# SJA1105Q_PINOUT.net
KiCad netlist of a schematic drawn in Altium Designer
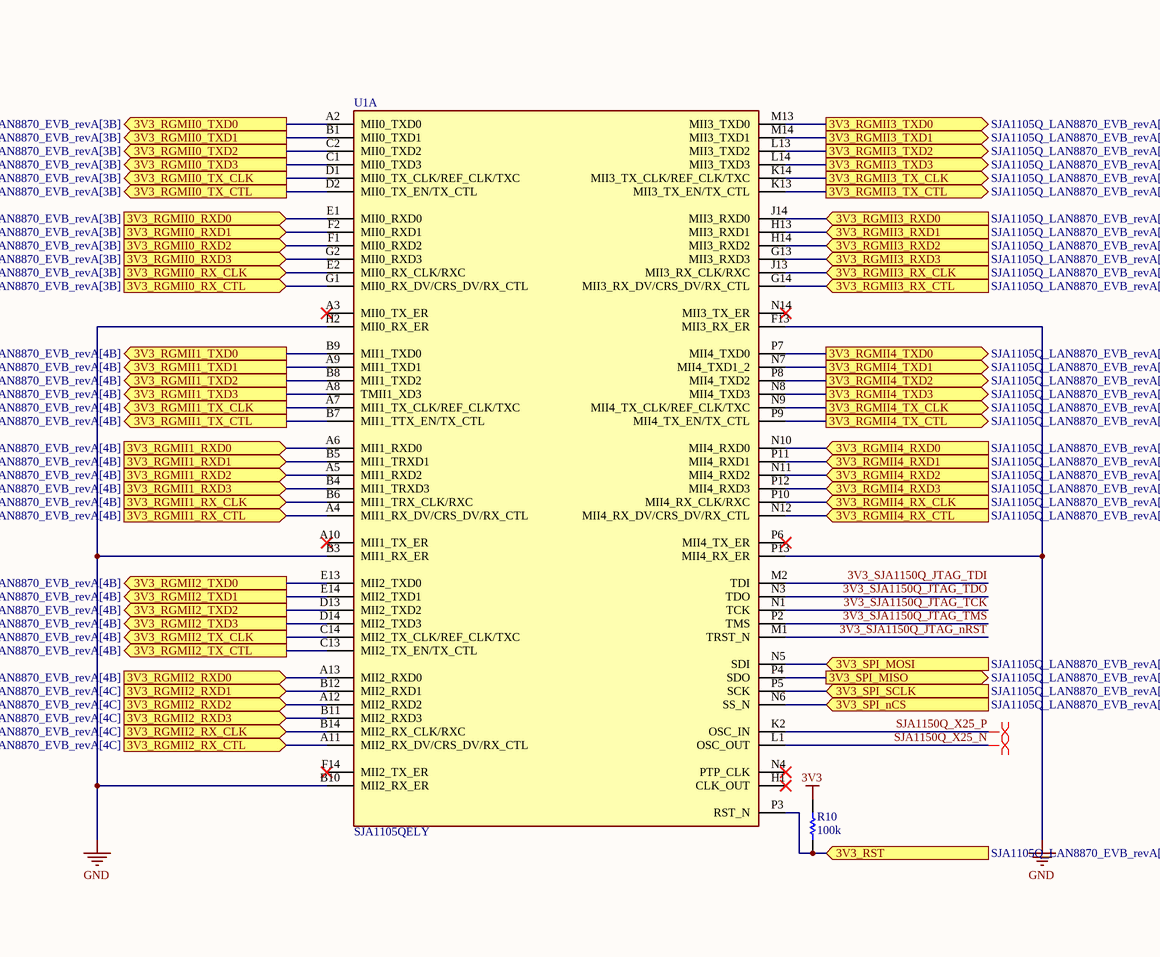
[diagram p0: SJA1105Q_PINOUT.SchDoc, top left]
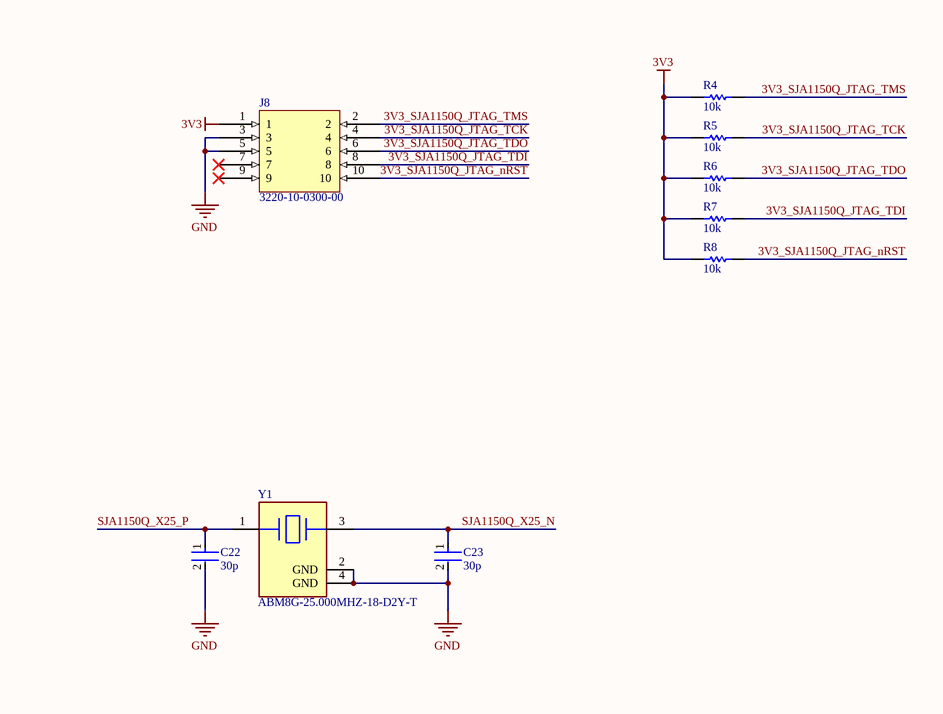
[diagram p1: SJA1105Q_PINOUT.SchDoc, top right]
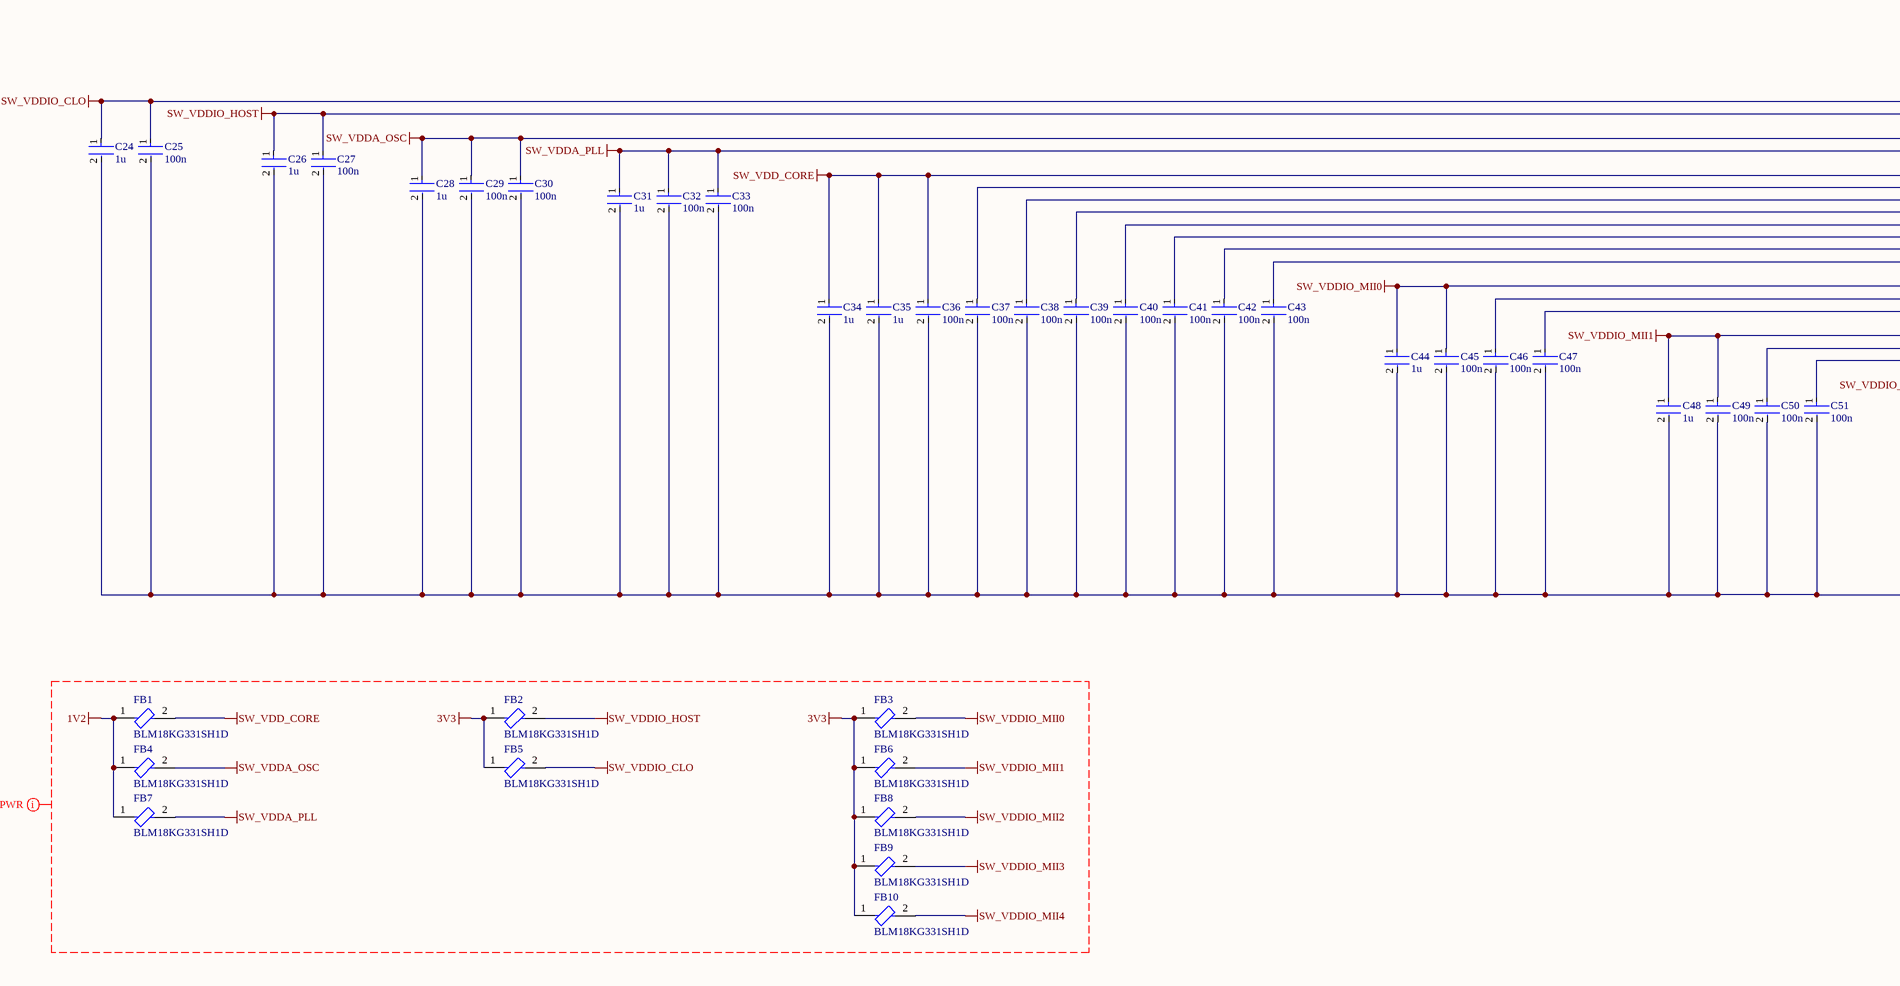
[diagram p2: SJA1105Q_PINOUT.SchDoc, bottom left]
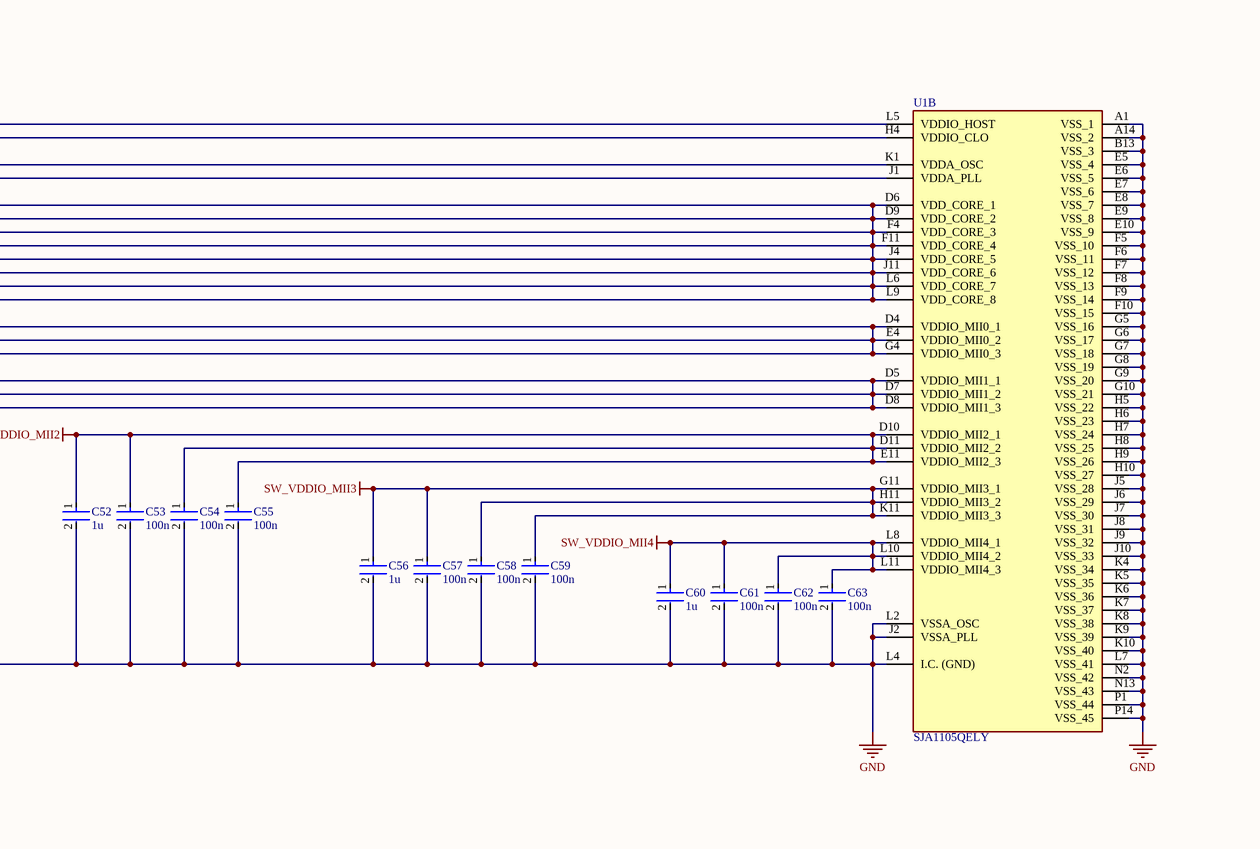
[diagram p3: SJA1105Q_PINOUT.SchDoc, bottom right]

(export (version "E")
  (design (tool "Eeschema 10.0.6"))
  (components
    (comp (ref "C22")
      (value "30p")
      (footprint "FP-0402-L_1_0_0_05-W_0_5-IPC_A")
      (description "LARGE PADS, 0402 CAP, CHANGE COMMENT TO MATCH REAL P/N")
      (libsource (lib "Space Concordia") (part "b4654b650e69147ec39a6b967a45e02"))
    )
    (comp (ref "C23")
      (value "30p")
      (footprint "FP-0402-L_1_0_0_05-W_0_5-IPC_A")
      (description "LARGE PADS, 0402 CAP, CHANGE COMMENT TO MATCH REAL P/N")
      (libsource (lib "Space Concordia") (part "b4654b650e69147ec39a6b967a45e02"))
    )
    (comp (ref "C24")
      (value "1u")
      (footprint "FP-0402-L_1_0_0_05-W_0_5-IPC_A")
      (description "LARGE PADS, 0402 CAP, CHANGE COMMENT TO MATCH REAL P/N")
      (libsource (lib "Space Concordia") (part "b4654b650e69147ec39a6b967a45e02"))
    )
    (comp (ref "C25")
      (value "100n")
      (footprint "FP-0402-L_1_0_0_05-W_0_5-IPC_A")
      (description "LARGE PADS, 0402 CAP, CHANGE COMMENT TO MATCH REAL P/N")
      (libsource (lib "Space Concordia") (part "b4654b650e69147ec39a6b967a45e02"))
    )
    (comp (ref "C26")
      (value "1u")
      (footprint "FP-0402-L_1_0_0_05-W_0_5-IPC_A")
      (description "LARGE PADS, 0402 CAP, CHANGE COMMENT TO MATCH REAL P/N")
      (libsource (lib "Space Concordia") (part "b4654b650e69147ec39a6b967a45e02"))
    )
    (comp (ref "C27")
      (value "100n")
      (footprint "FP-0402-L_1_0_0_05-W_0_5-IPC_A")
      (description "LARGE PADS, 0402 CAP, CHANGE COMMENT TO MATCH REAL P/N")
      (libsource (lib "Space Concordia") (part "b4654b650e69147ec39a6b967a45e02"))
    )
    (comp (ref "C28")
      (value "1u")
      (footprint "FP-0402-L_1_0_0_05-W_0_5-IPC_A")
      (description "LARGE PADS, 0402 CAP, CHANGE COMMENT TO MATCH REAL P/N")
      (libsource (lib "Space Concordia") (part "b4654b650e69147ec39a6b967a45e02"))
    )
    (comp (ref "C29")
      (value "100n")
      (footprint "FP-0402-L_1_0_0_05-W_0_5-IPC_A")
      (description "LARGE PADS, 0402 CAP, CHANGE COMMENT TO MATCH REAL P/N")
      (libsource (lib "Space Concordia") (part "b4654b650e69147ec39a6b967a45e02"))
    )
    (comp (ref "C30")
      (value "100n")
      (footprint "FP-0402-L_1_0_0_05-W_0_5-IPC_A")
      (description "LARGE PADS, 0402 CAP, CHANGE COMMENT TO MATCH REAL P/N")
      (libsource (lib "Space Concordia") (part "b4654b650e69147ec39a6b967a45e02"))
    )
    (comp (ref "C31")
      (value "1u")
      (footprint "FP-0402-L_1_0_0_05-W_0_5-IPC_A")
      (description "LARGE PADS, 0402 CAP, CHANGE COMMENT TO MATCH REAL P/N")
      (libsource (lib "Space Concordia") (part "b4654b650e69147ec39a6b967a45e02"))
    )
    (comp (ref "C32")
      (value "100n")
      (footprint "FP-0402-L_1_0_0_05-W_0_5-IPC_A")
      (description "LARGE PADS, 0402 CAP, CHANGE COMMENT TO MATCH REAL P/N")
      (libsource (lib "Space Concordia") (part "b4654b650e69147ec39a6b967a45e02"))
    )
    (comp (ref "C33")
      (value "100n")
      (footprint "FP-0402-L_1_0_0_05-W_0_5-IPC_A")
      (description "LARGE PADS, 0402 CAP, CHANGE COMMENT TO MATCH REAL P/N")
      (libsource (lib "Space Concordia") (part "b4654b650e69147ec39a6b967a45e02"))
    )
    (comp (ref "C34")
      (value "1u")
      (footprint "FP-0402-L_1_0_0_05-W_0_5-IPC_A")
      (description "LARGE PADS, 0402 CAP, CHANGE COMMENT TO MATCH REAL P/N")
      (libsource (lib "Space Concordia") (part "b4654b650e69147ec39a6b967a45e02"))
    )
    (comp (ref "C35")
      (value "1u")
      (footprint "FP-0402-L_1_0_0_05-W_0_5-IPC_A")
      (description "LARGE PADS, 0402 CAP, CHANGE COMMENT TO MATCH REAL P/N")
      (libsource (lib "Space Concordia") (part "b4654b650e69147ec39a6b967a45e02"))
    )
    (comp (ref "C36")
      (value "100n")
      (footprint "FP-0402-L_1_0_0_05-W_0_5-IPC_A")
      (description "LARGE PADS, 0402 CAP, CHANGE COMMENT TO MATCH REAL P/N")
      (libsource (lib "Space Concordia") (part "b4654b650e69147ec39a6b967a45e02"))
    )
    (comp (ref "C37")
      (value "100n")
      (footprint "FP-0402-L_1_0_0_05-W_0_5-IPC_A")
      (description "LARGE PADS, 0402 CAP, CHANGE COMMENT TO MATCH REAL P/N")
      (libsource (lib "Space Concordia") (part "b4654b650e69147ec39a6b967a45e02"))
    )
    (comp (ref "C38")
      (value "100n")
      (footprint "FP-0402-L_1_0_0_05-W_0_5-IPC_A")
      (description "LARGE PADS, 0402 CAP, CHANGE COMMENT TO MATCH REAL P/N")
      (libsource (lib "Space Concordia") (part "b4654b650e69147ec39a6b967a45e02"))
    )
    (comp (ref "C39")
      (value "100n")
      (footprint "FP-0402-L_1_0_0_05-W_0_5-IPC_A")
      (description "LARGE PADS, 0402 CAP, CHANGE COMMENT TO MATCH REAL P/N")
      (libsource (lib "Space Concordia") (part "b4654b650e69147ec39a6b967a45e02"))
    )
    (comp (ref "C40")
      (value "100n")
      (footprint "FP-0402-L_1_0_0_05-W_0_5-IPC_A")
      (description "LARGE PADS, 0402 CAP, CHANGE COMMENT TO MATCH REAL P/N")
      (libsource (lib "Space Concordia") (part "b4654b650e69147ec39a6b967a45e02"))
    )
    (comp (ref "C41")
      (value "100n")
      (footprint "FP-0402-L_1_0_0_05-W_0_5-IPC_A")
      (description "LARGE PADS, 0402 CAP, CHANGE COMMENT TO MATCH REAL P/N")
      (libsource (lib "Space Concordia") (part "b4654b650e69147ec39a6b967a45e02"))
    )
    (comp (ref "C42")
      (value "100n")
      (footprint "FP-0402-L_1_0_0_05-W_0_5-IPC_A")
      (description "LARGE PADS, 0402 CAP, CHANGE COMMENT TO MATCH REAL P/N")
      (libsource (lib "Space Concordia") (part "b4654b650e69147ec39a6b967a45e02"))
    )
    (comp (ref "C43")
      (value "100n")
      (footprint "FP-0402-L_1_0_0_05-W_0_5-IPC_A")
      (description "LARGE PADS, 0402 CAP, CHANGE COMMENT TO MATCH REAL P/N")
      (libsource (lib "Space Concordia") (part "b4654b650e69147ec39a6b967a45e02"))
    )
    (comp (ref "C44")
      (value "1u")
      (footprint "FP-0402-L_1_0_0_05-W_0_5-IPC_A")
      (description "LARGE PADS, 0402 CAP, CHANGE COMMENT TO MATCH REAL P/N")
      (libsource (lib "Space Concordia") (part "b4654b650e69147ec39a6b967a45e02"))
    )
    (comp (ref "C45")
      (value "100n")
      (footprint "FP-0402-L_1_0_0_05-W_0_5-IPC_A")
      (description "LARGE PADS, 0402 CAP, CHANGE COMMENT TO MATCH REAL P/N")
      (libsource (lib "Space Concordia") (part "b4654b650e69147ec39a6b967a45e02"))
    )
    (comp (ref "C46")
      (value "100n")
      (footprint "FP-0402-L_1_0_0_05-W_0_5-IPC_A")
      (description "LARGE PADS, 0402 CAP, CHANGE COMMENT TO MATCH REAL P/N")
      (libsource (lib "Space Concordia") (part "b4654b650e69147ec39a6b967a45e02"))
    )
    (comp (ref "C47")
      (value "100n")
      (footprint "FP-0402-L_1_0_0_05-W_0_5-IPC_A")
      (description "LARGE PADS, 0402 CAP, CHANGE COMMENT TO MATCH REAL P/N")
      (libsource (lib "Space Concordia") (part "b4654b650e69147ec39a6b967a45e02"))
    )
    (comp (ref "C48")
      (value "1u")
      (footprint "FP-0402-L_1_0_0_05-W_0_5-IPC_A")
      (description "LARGE PADS, 0402 CAP, CHANGE COMMENT TO MATCH REAL P/N")
      (libsource (lib "Space Concordia") (part "b4654b650e69147ec39a6b967a45e02"))
    )
    (comp (ref "C49")
      (value "100n")
      (footprint "FP-0402-L_1_0_0_05-W_0_5-IPC_A")
      (description "LARGE PADS, 0402 CAP, CHANGE COMMENT TO MATCH REAL P/N")
      (libsource (lib "Space Concordia") (part "b4654b650e69147ec39a6b967a45e02"))
    )
    (comp (ref "C50")
      (value "100n")
      (footprint "FP-0402-L_1_0_0_05-W_0_5-IPC_A")
      (description "LARGE PADS, 0402 CAP, CHANGE COMMENT TO MATCH REAL P/N")
      (libsource (lib "Space Concordia") (part "b4654b650e69147ec39a6b967a45e02"))
    )
    (comp (ref "C51")
      (value "100n")
      (footprint "FP-0402-L_1_0_0_05-W_0_5-IPC_A")
      (description "LARGE PADS, 0402 CAP, CHANGE COMMENT TO MATCH REAL P/N")
      (libsource (lib "Space Concordia") (part "b4654b650e69147ec39a6b967a45e02"))
    )
    (comp (ref "C52")
      (value "1u")
      (footprint "FP-0402-L_1_0_0_05-W_0_5-IPC_A")
      (description "LARGE PADS, 0402 CAP, CHANGE COMMENT TO MATCH REAL P/N")
      (libsource (lib "Space Concordia") (part "b4654b650e69147ec39a6b967a45e02"))
    )
    (comp (ref "C53")
      (value "100n")
      (footprint "FP-0402-L_1_0_0_05-W_0_5-IPC_A")
      (description "LARGE PADS, 0402 CAP, CHANGE COMMENT TO MATCH REAL P/N")
      (libsource (lib "Space Concordia") (part "b4654b650e69147ec39a6b967a45e02"))
    )
    (comp (ref "C54")
      (value "100n")
      (footprint "FP-0402-L_1_0_0_05-W_0_5-IPC_A")
      (description "LARGE PADS, 0402 CAP, CHANGE COMMENT TO MATCH REAL P/N")
      (libsource (lib "Space Concordia") (part "b4654b650e69147ec39a6b967a45e02"))
    )
    (comp (ref "C55")
      (value "100n")
      (footprint "FP-0402-L_1_0_0_05-W_0_5-IPC_A")
      (description "LARGE PADS, 0402 CAP, CHANGE COMMENT TO MATCH REAL P/N")
      (libsource (lib "Space Concordia") (part "b4654b650e69147ec39a6b967a45e02"))
    )
    (comp (ref "C56")
      (value "1u")
      (footprint "FP-0402-L_1_0_0_05-W_0_5-IPC_A")
      (description "LARGE PADS, 0402 CAP, CHANGE COMMENT TO MATCH REAL P/N")
      (libsource (lib "Space Concordia") (part "b4654b650e69147ec39a6b967a45e02"))
    )
    (comp (ref "C57")
      (value "100n")
      (footprint "FP-0402-L_1_0_0_05-W_0_5-IPC_A")
      (description "LARGE PADS, 0402 CAP, CHANGE COMMENT TO MATCH REAL P/N")
      (libsource (lib "Space Concordia") (part "b4654b650e69147ec39a6b967a45e02"))
    )
    (comp (ref "C58")
      (value "100n")
      (footprint "FP-0402-L_1_0_0_05-W_0_5-IPC_A")
      (description "LARGE PADS, 0402 CAP, CHANGE COMMENT TO MATCH REAL P/N")
      (libsource (lib "Space Concordia") (part "b4654b650e69147ec39a6b967a45e02"))
    )
    (comp (ref "C59")
      (value "100n")
      (footprint "FP-0402-L_1_0_0_05-W_0_5-IPC_A")
      (description "LARGE PADS, 0402 CAP, CHANGE COMMENT TO MATCH REAL P/N")
      (libsource (lib "Space Concordia") (part "b4654b650e69147ec39a6b967a45e02"))
    )
    (comp (ref "C60")
      (value "1u")
      (footprint "FP-0402-L_1_0_0_05-W_0_5-IPC_A")
      (description "LARGE PADS, 0402 CAP, CHANGE COMMENT TO MATCH REAL P/N")
      (libsource (lib "Space Concordia") (part "b4654b650e69147ec39a6b967a45e02"))
    )
    (comp (ref "C61")
      (value "100n")
      (footprint "FP-0402-L_1_0_0_05-W_0_5-IPC_A")
      (description "LARGE PADS, 0402 CAP, CHANGE COMMENT TO MATCH REAL P/N")
      (libsource (lib "Space Concordia") (part "b4654b650e69147ec39a6b967a45e02"))
    )
    (comp (ref "C62")
      (value "100n")
      (footprint "FP-0402-L_1_0_0_05-W_0_5-IPC_A")
      (description "LARGE PADS, 0402 CAP, CHANGE COMMENT TO MATCH REAL P/N")
      (libsource (lib "Space Concordia") (part "b4654b650e69147ec39a6b967a45e02"))
    )
    (comp (ref "C63")
      (value "100n")
      (footprint "FP-0402-L_1_0_0_05-W_0_5-IPC_A")
      (description "LARGE PADS, 0402 CAP, CHANGE COMMENT TO MATCH REAL P/N")
      (libsource (lib "Space Concordia") (part "b4654b650e69147ec39a6b967a45e02"))
    )
    (comp (ref "FB1")
      (value "BLM18KG331SH1D")
      (footprint "FP-BLM18-0_15-t0_8-IPC_B")
      (description "Chip Ferrite Bead, 0603, 330Ω @ 100MHz, 0.08Ω, 25%, 1.7A")
      (libsource (lib "Altium Content Vault") (part "5f30dd21d616792df468990f7003faa"))
    )
    (comp (ref "FB2")
      (value "BLM18KG331SH1D")
      (footprint "FP-BLM18-0_15-t0_8-IPC_B")
      (description "Chip Ferrite Bead, 0603, 330Ω @ 100MHz, 0.08Ω, 25%, 1.7A")
      (libsource (lib "Altium Content Vault") (part "5f30dd21d616792df468990f7003faa"))
    )
    (comp (ref "FB3")
      (value "BLM18KG331SH1D")
      (footprint "FP-BLM18-0_15-t0_8-IPC_B")
      (description "Chip Ferrite Bead, 0603, 330Ω @ 100MHz, 0.08Ω, 25%, 1.7A")
      (libsource (lib "Altium Content Vault") (part "5f30dd21d616792df468990f7003faa"))
    )
    (comp (ref "FB4")
      (value "BLM18KG331SH1D")
      (footprint "FP-BLM18-0_15-t0_8-IPC_B")
      (description "Chip Ferrite Bead, 0603, 330Ω @ 100MHz, 0.08Ω, 25%, 1.7A")
      (libsource (lib "Altium Content Vault") (part "5f30dd21d616792df468990f7003faa"))
    )
    (comp (ref "FB5")
      (value "BLM18KG331SH1D")
      (footprint "FP-BLM18-0_15-t0_8-IPC_B")
      (description "Chip Ferrite Bead, 0603, 330Ω @ 100MHz, 0.08Ω, 25%, 1.7A")
      (libsource (lib "Altium Content Vault") (part "5f30dd21d616792df468990f7003faa"))
    )
    (comp (ref "FB6")
      (value "BLM18KG331SH1D")
      (footprint "FP-BLM18-0_15-t0_8-IPC_B")
      (description "Chip Ferrite Bead, 0603, 330Ω @ 100MHz, 0.08Ω, 25%, 1.7A")
      (libsource (lib "Altium Content Vault") (part "5f30dd21d616792df468990f7003faa"))
    )
    (comp (ref "FB7")
      (value "BLM18KG331SH1D")
      (footprint "FP-BLM18-0_15-t0_8-IPC_B")
      (description "Chip Ferrite Bead, 0603, 330Ω @ 100MHz, 0.08Ω, 25%, 1.7A")
      (libsource (lib "Altium Content Vault") (part "5f30dd21d616792df468990f7003faa"))
    )
    (comp (ref "FB8")
      (value "BLM18KG331SH1D")
      (footprint "FP-BLM18-0_15-t0_8-IPC_B")
      (description "Chip Ferrite Bead, 0603, 330Ω @ 100MHz, 0.08Ω, 25%, 1.7A")
      (libsource (lib "Altium Content Vault") (part "5f30dd21d616792df468990f7003faa"))
    )
    (comp (ref "FB9")
      (value "BLM18KG331SH1D")
      (footprint "FP-BLM18-0_15-t0_8-IPC_B")
      (description "Chip Ferrite Bead, 0603, 330Ω @ 100MHz, 0.08Ω, 25%, 1.7A")
      (libsource (lib "Altium Content Vault") (part "5f30dd21d616792df468990f7003faa"))
    )
    (comp (ref "FB10")
      (value "BLM18KG331SH1D")
      (footprint "FP-BLM18-0_15-t0_8-IPC_B")
      (description "Chip Ferrite Bead, 0603, 330Ω @ 100MHz, 0.08Ω, 25%, 1.7A")
      (libsource (lib "Altium Content Vault") (part "5f30dd21d616792df468990f7003faa"))
    )
    (comp (ref "J8")
      (value "3220-10-0300-00")
      (footprint "3220-10-0300-00-Footprint-1")
      (description "CONN HEADER SMD 10POS 1.27MM")
      (libsource (lib "Space Concordia") (part "3220-10-0300-00"))
    )
    (comp (ref "R4")
      (value "10k")
      (footprint "R0603B")
      (description "Resistor")
      (libsource (lib "Space Concordia") (part "Resistor"))
    )
    (comp (ref "R5")
      (value "10k")
      (footprint "R0603B")
      (description "Resistor")
      (libsource (lib "Space Concordia") (part "Resistor"))
    )
    (comp (ref "R6")
      (value "10k")
      (footprint "R0603B")
      (description "Resistor")
      (libsource (lib "Space Concordia") (part "Resistor"))
    )
    (comp (ref "R7")
      (value "10k")
      (footprint "R0603B")
      (description "Resistor")
      (libsource (lib "Space Concordia") (part "Resistor"))
    )
    (comp (ref "R8")
      (value "10k")
      (footprint "R0603B")
      (description "Resistor")
      (libsource (lib "Space Concordia") (part "Resistor"))
    )
    (comp (ref "R10")
      (value "100k")
      (footprint "R0603B")
      (description "Resistor")
      (libsource (lib "Space Concordia") (part "Resistor"))
    )
    (comp (ref "U1")
      (value "SJA1105QELY")
      (footprint "SJA1105QELY-Footprint-1")
      (description "Ethernet Controller, Ethernet Switch, IEEE 802.3, 1.2 V, LFBGA, 159 Pins")
      (libsource (lib "Space Concordia") (part "SJA1105QELY"))
    )
    (comp (ref "Y1")
      (value "ABM8G-25.000MHZ-18-D2Y-T")
      (footprint "FP-ABM8G-MFG")
      (description "Crystal 25MHz ±20ppm (Tol) ±30ppm (Stability) 18pF FUND 60Ω 4-Pin SMD T/R")
      (fields (field (name "TOLERANCE") "20ppm"))
      (libsource (lib "Altium Content Vault") (part "48e526d86b7f2615d98721063c72f49"))
    )
  )
  (nets
    (net (code "1") (name "/3V3_RGMII0_RXD0") (class "Default")
      (node (ref "U1") (pin "E1") (pinfunction "MII0_RXD0_E1") (pintype "passive"))
    )
    (net (code "2") (name "/3V3_RGMII0_RXD1") (class "Default")
      (node (ref "U1") (pin "F2") (pinfunction "MII0_RXD1_F2") (pintype "passive"))
    )
    (net (code "3") (name "/3V3_RGMII0_RXD2") (class "Default")
      (node (ref "U1") (pin "F1") (pinfunction "MII0_RXD2_F1") (pintype "passive"))
    )
    (net (code "4") (name "/3V3_RGMII0_RXD3") (class "Default")
      (node (ref "U1") (pin "G2") (pinfunction "MII0_RXD3_G2") (pintype "passive"))
    )
    (net (code "5") (name "/3V3_RGMII0_RX_CLK") (class "Default")
      (node (ref "U1") (pin "E2") (pinfunction "MII0_RX_CLK/RXC_E2") (pintype "passive"))
    )
    (net (code "6") (name "/3V3_RGMII0_RX_CTL") (class "Default")
      (node (ref "U1") (pin "G1") (pinfunction "MII0_RX_DV/CRS_DV/RX_CTL_G1") (pintype "passive"))
    )
    (net (code "7") (name "/3V3_RGMII0_TXD0") (class "Default")
      (node (ref "U1") (pin "A2") (pinfunction "MII0_TXD0_A2") (pintype "passive"))
    )
    (net (code "8") (name "/3V3_RGMII0_TXD1") (class "Default")
      (node (ref "U1") (pin "B1") (pinfunction "MII0_TXD1_B1") (pintype "passive"))
    )
    (net (code "9") (name "/3V3_RGMII0_TXD2") (class "Default")
      (node (ref "U1") (pin "C2") (pinfunction "MII0_TXD2_C2") (pintype "passive"))
    )
    (net (code "10") (name "/3V3_RGMII0_TXD3") (class "Default")
      (node (ref "U1") (pin "C1") (pinfunction "MII0_TXD3_C1") (pintype "passive"))
    )
    (net (code "11") (name "/3V3_RGMII0_TX_CLK") (class "Default")
      (node (ref "U1") (pin "D1") (pinfunction "MII0_TX_CLK/REF_CLK/TXC_D1") (pintype "passive"))
    )
    (net (code "12") (name "/3V3_RGMII0_TX_CTL") (class "Default")
      (node (ref "U1") (pin "D2") (pinfunction "MII0_TX_EN/TX_CTL_D2") (pintype "passive"))
    )
    (net (code "13") (name "/3V3_RGMII1_RXD0") (class "Default")
      (node (ref "U1") (pin "A6") (pinfunction "MII1_RXD0_A6") (pintype "passive"))
    )
    (net (code "14") (name "/3V3_RGMII1_RXD1") (class "Default")
      (node (ref "U1") (pin "B5") (pinfunction "MII1_TRXD1_B5") (pintype "passive"))
    )
    (net (code "15") (name "/3V3_RGMII1_RXD2") (class "Default")
      (node (ref "U1") (pin "A5") (pinfunction "MII1_RXD2_A5") (pintype "passive"))
    )
    (net (code "16") (name "/3V3_RGMII1_RXD3") (class "Default")
      (node (ref "U1") (pin "B4") (pinfunction "MII1_TRXD3_B4") (pintype "passive"))
    )
    (net (code "17") (name "/3V3_RGMII1_RX_CLK") (class "Default")
      (node (ref "U1") (pin "B6") (pinfunction "MII1_TRX_CLK/RXC_B6") (pintype "passive"))
    )
    (net (code "18") (name "/3V3_RGMII1_RX_CTL") (class "Default")
      (node (ref "U1") (pin "A4") (pinfunction "MII1_RX_DV/CRS_DV/RX_CTL_A4") (pintype "passive"))
    )
    (net (code "19") (name "/3V3_RGMII1_TXD0") (class "Default")
      (node (ref "U1") (pin "B9") (pinfunction "MII1_TXD0_B9") (pintype "passive"))
    )
    (net (code "20") (name "/3V3_RGMII1_TXD1") (class "Default")
      (node (ref "U1") (pin "A9") (pinfunction "MII1_TXD1_A9") (pintype "passive"))
    )
    (net (code "21") (name "/3V3_RGMII1_TXD2") (class "Default")
      (node (ref "U1") (pin "B8") (pinfunction "MII1_TXD2_B8") (pintype "passive"))
    )
    (net (code "22") (name "/3V3_RGMII1_TXD3") (class "Default")
      (node (ref "U1") (pin "A8") (pinfunction "TMII1_XD3_A8") (pintype "passive"))
    )
    (net (code "23") (name "/3V3_RGMII1_TX_CLK") (class "Default")
      (node (ref "U1") (pin "A7") (pinfunction "MII1_TX_CLK/REF_CLK/TXC_A7") (pintype "passive"))
    )
    (net (code "24") (name "/3V3_RGMII1_TX_CTL") (class "Default")
      (node (ref "U1") (pin "B7") (pinfunction "MII1_TTX_EN/TX_CTL_B7") (pintype "passive"))
    )
    (net (code "25") (name "/3V3_RGMII2_RXD0") (class "Default")
      (node (ref "U1") (pin "A13") (pinfunction "MII2_RXD0_A13") (pintype "passive"))
    )
    (net (code "26") (name "/3V3_RGMII2_RXD1") (class "Default")
      (node (ref "U1") (pin "B12") (pinfunction "MII2_RXD1_B12") (pintype "passive"))
    )
    (net (code "27") (name "/3V3_RGMII2_RXD2") (class "Default")
      (node (ref "U1") (pin "A12") (pinfunction "MII2_RXD2_A12") (pintype "passive"))
    )
    (net (code "28") (name "/3V3_RGMII2_RXD3") (class "Default")
      (node (ref "U1") (pin "B11") (pinfunction "MII2_RXD3_B11") (pintype "passive"))
    )
    (net (code "29") (name "/3V3_RGMII2_RX_CLK") (class "Default")
      (node (ref "U1") (pin "B14") (pinfunction "MII2_RX_CLK/RXC_B14") (pintype "passive"))
    )
    (net (code "30") (name "/3V3_RGMII2_RX_CTL") (class "Default")
      (node (ref "U1") (pin "A11") (pinfunction "MII2_RX_DV/CRS_DV/RX_CTL_A11") (pintype "passive"))
    )
    (net (code "31") (name "/3V3_RGMII2_TXD0") (class "Default")
      (node (ref "U1") (pin "E13") (pinfunction "MII2_TXD0_E13") (pintype "passive"))
    )
    (net (code "32") (name "/3V3_RGMII2_TXD1") (class "Default")
      (node (ref "U1") (pin "E14") (pinfunction "MII2_TXD1_E14") (pintype "passive"))
    )
    (net (code "33") (name "/3V3_RGMII2_TXD2") (class "Default")
      (node (ref "U1") (pin "D13") (pinfunction "MII2_TXD2_D13") (pintype "passive"))
    )
    (net (code "34") (name "/3V3_RGMII2_TXD3") (class "Default")
      (node (ref "U1") (pin "D14") (pinfunction "MII2_TXD3_D14") (pintype "passive"))
    )
    (net (code "35") (name "/3V3_RGMII2_TX_CLK") (class "Default")
      (node (ref "U1") (pin "C14") (pinfunction "MII2_TX_CLK/REF_CLK/TXC_C14") (pintype "passive"))
    )
    (net (code "36") (name "/3V3_RGMII2_TX_CTL") (class "Default")
      (node (ref "U1") (pin "C13") (pinfunction "MII2_TX_EN/TX_CTL_C13") (pintype "passive"))
    )
    (net (code "37") (name "/3V3_RGMII3_RXD0") (class "Default")
      (node (ref "U1") (pin "J14") (pinfunction "MII3_RXD0_J14") (pintype "passive"))
    )
    (net (code "38") (name "/3V3_RGMII3_RXD1") (class "Default")
      (node (ref "U1") (pin "H13") (pinfunction "MII3_RXD1_H13") (pintype "passive"))
    )
    (net (code "39") (name "/3V3_RGMII3_RXD2") (class "Default")
      (node (ref "U1") (pin "H14") (pinfunction "MII3_RXD2_H14") (pintype "passive"))
    )
    (net (code "40") (name "/3V3_RGMII3_RXD3") (class "Default")
      (node (ref "U1") (pin "G13") (pinfunction "MII3_RXD3_G13") (pintype "passive"))
    )
    (net (code "41") (name "/3V3_RGMII3_RX_CLK") (class "Default")
      (node (ref "U1") (pin "J13") (pinfunction "MII3_RX_CLK/RXC_J13") (pintype "passive"))
    )
    (net (code "42") (name "/3V3_RGMII3_RX_CTL") (class "Default")
      (node (ref "U1") (pin "G14") (pinfunction "MII3_RX_DV/CRS_DV/RX_CTL_G14") (pintype "passive"))
    )
    (net (code "43") (name "/3V3_RGMII3_TXD0") (class "Default")
      (node (ref "U1") (pin "M13") (pinfunction "MII3_TXD0_M13") (pintype "passive"))
    )
    (net (code "44") (name "/3V3_RGMII3_TXD1") (class "Default")
      (node (ref "U1") (pin "M14") (pinfunction "MII3_TXD1_M14") (pintype "passive"))
    )
    (net (code "45") (name "/3V3_RGMII3_TXD2") (class "Default")
      (node (ref "U1") (pin "L13") (pinfunction "MII3_TXD2_L13") (pintype "passive"))
    )
    (net (code "46") (name "/3V3_RGMII3_TXD3") (class "Default")
      (node (ref "U1") (pin "L14") (pinfunction "MII3_TXD3_L14") (pintype "passive"))
    )
    (net (code "47") (name "/3V3_RGMII3_TX_CLK") (class "Default")
      (node (ref "U1") (pin "K14") (pinfunction "MII3_TX_CLK/REF_CLK/TXC_K14") (pintype "passive"))
    )
    (net (code "48") (name "/3V3_RGMII3_TX_CTL") (class "Default")
      (node (ref "U1") (pin "K13") (pinfunction "MII3_TX_EN/TX_CTL_K13") (pintype "passive"))
    )
    (net (code "49") (name "/3V3_RGMII4_RXD0") (class "Default")
      (node (ref "U1") (pin "N10") (pinfunction "MII4_RXD0_N10") (pintype "passive"))
    )
    (net (code "50") (name "/3V3_RGMII4_RXD1") (class "Default")
      (node (ref "U1") (pin "P11") (pinfunction "MII4_RXD1_P11") (pintype "passive"))
    )
    (net (code "51") (name "/3V3_RGMII4_RXD2") (class "Default")
      (node (ref "U1") (pin "N11") (pinfunction "MII4_RXD2_N11") (pintype "passive"))
    )
    (net (code "52") (name "/3V3_RGMII4_RXD3") (class "Default")
      (node (ref "U1") (pin "P12") (pinfunction "MII4_RXD3_P12") (pintype "passive"))
    )
    (net (code "53") (name "/3V3_RGMII4_RX_CLK") (class "Default")
      (node (ref "U1") (pin "P10") (pinfunction "MII4_RX_CLK/RXC_P10") (pintype "passive"))
    )
    (net (code "54") (name "/3V3_RGMII4_RX_CTL") (class "Default")
      (node (ref "U1") (pin "N12") (pinfunction "MII4_RX_DV/CRS_DV/RX_CTL_N12") (pintype "passive"))
    )
    (net (code "55") (name "/3V3_RGMII4_TXD0") (class "Default")
      (node (ref "U1") (pin "P7") (pinfunction "MII4_TXD0_P7") (pintype "passive"))
    )
    (net (code "56") (name "/3V3_RGMII4_TXD1") (class "Default")
      (node (ref "U1") (pin "N7") (pinfunction "MII4_TXD1_2_N7") (pintype "passive"))
    )
    (net (code "57") (name "/3V3_RGMII4_TXD2") (class "Default")
      (node (ref "U1") (pin "P8") (pinfunction "MII4_TXD2_P8") (pintype "passive"))
    )
    (net (code "58") (name "/3V3_RGMII4_TXD3") (class "Default")
      (node (ref "U1") (pin "N8") (pinfunction "MII4_TXD3_N8") (pintype "passive"))
    )
    (net (code "59") (name "/3V3_RGMII4_TX_CLK") (class "Default")
      (node (ref "U1") (pin "N9") (pinfunction "MII4_TX_CLK/REF_CLK/TXC_N9") (pintype "passive"))
    )
    (net (code "60") (name "/3V3_RGMII4_TX_CTL") (class "Default")
      (node (ref "U1") (pin "P9") (pinfunction "MII4_TX_EN/TX_CTL_P9") (pintype "passive"))
    )
    (net (code "61") (name "/3V3_RST") (class "Default")
      (node (ref "R10") (pin "1") (pinfunction "1_1") (pintype "passive"))
      (node (ref "U1") (pin "P3") (pinfunction "RST_N_P3") (pintype "passive"))
    )
    (net (code "62") (name "/3V3_SJA1150Q_JTAG_TCK") (class "Default")
      (node (ref "J8") (pin "4") (pinfunction "4_4") (pintype "input"))
      (node (ref "R5") (pin "2") (pinfunction "2_2") (pintype "passive"))
      (node (ref "U1") (pin "N1") (pinfunction "TCK_N1") (pintype "passive"))
    )
    (net (code "63") (name "/3V3_SJA1150Q_JTAG_TDI") (class "Default")
      (node (ref "J8") (pin "8") (pinfunction "8_8") (pintype "input"))
      (node (ref "R7") (pin "1") (pinfunction "1_1") (pintype "passive"))
      (node (ref "U1") (pin "M2") (pinfunction "TDI_M2") (pintype "passive"))
    )
    (net (code "64") (name "/3V3_SJA1150Q_JTAG_TDO") (class "Default")
      (node (ref "J8") (pin "6") (pinfunction "6_6") (pintype "input"))
      (node (ref "R6") (pin "2") (pinfunction "2_2") (pintype "passive"))
      (node (ref "U1") (pin "N3") (pinfunction "TDO_N3") (pintype "passive"))
    )
    (net (code "65") (name "/3V3_SJA1150Q_JTAG_TMS") (class "Default")
      (node (ref "J8") (pin "2") (pinfunction "2_2") (pintype "input"))
      (node (ref "R4") (pin "2") (pinfunction "2_2") (pintype "passive"))
      (node (ref "U1") (pin "P2") (pinfunction "TMS_P2") (pintype "passive"))
    )
    (net (code "66") (name "/3V3_SJA1150Q_JTAG_nRST") (class "Default")
      (node (ref "J8") (pin "10") (pinfunction "10_10") (pintype "input"))
      (node (ref "R8") (pin "2") (pinfunction "2_2") (pintype "passive"))
      (node (ref "U1") (pin "M1") (pinfunction "TRST_N_M1") (pintype "passive"))
    )
    (net (code "67") (name "/3V3_SPI_MISO") (class "Default")
      (node (ref "U1") (pin "P4") (pinfunction "SDO_P4") (pintype "passive"))
    )
    (net (code "68") (name "/3V3_SPI_MOSI") (class "Default")
      (node (ref "U1") (pin "N5") (pinfunction "SDI_N5") (pintype "passive"))
    )
    (net (code "69") (name "/3V3_SPI_SCLK") (class "Default")
      (node (ref "U1") (pin "P5") (pinfunction "SCK_P5") (pintype "passive"))
    )
    (net (code "70") (name "/3V3_SPI_nCS") (class "Default")
      (node (ref "U1") (pin "N6") (pinfunction "SS_N_N6") (pintype "passive"))
    )
    (net (code "71") (name "/SJA1150Q_X25_N") (class "Default")
      (node (ref "C23") (pin "1") (pinfunction "1_1") (pintype "passive"))
      (node (ref "U1") (pin "L1") (pinfunction "OSC_OUT_L1") (pintype "passive"))
      (node (ref "Y1") (pin "3") (pinfunction "3_3") (pintype "passive"))
    )
    (net (code "72") (name "/SJA1150Q_X25_P") (class "Default")
      (node (ref "C22") (pin "1") (pinfunction "1_1") (pintype "passive"))
      (node (ref "U1") (pin "K2") (pinfunction "OSC_IN_K2") (pintype "passive"))
      (node (ref "Y1") (pin "1") (pinfunction "1_1") (pintype "passive"))
    )
    (net (code "73") (name "1V2") (class "Default")
      (node (ref "FB1") (pin "1") (pinfunction "1_1") (pintype "passive"))
      (node (ref "FB4") (pin "1") (pinfunction "1_1") (pintype "passive"))
      (node (ref "FB7") (pin "1") (pinfunction "1_1") (pintype "passive"))
    )
    (net (code "74") (name "3V3") (class "Default")
      (node (ref "FB10") (pin "1") (pinfunction "1_1") (pintype "passive"))
      (node (ref "FB2") (pin "1") (pinfunction "1_1") (pintype "passive"))
      (node (ref "FB3") (pin "1") (pinfunction "1_1") (pintype "passive"))
      (node (ref "FB5") (pin "1") (pinfunction "1_1") (pintype "passive"))
      (node (ref "FB6") (pin "1") (pinfunction "1_1") (pintype "passive"))
      (node (ref "FB8") (pin "1") (pinfunction "1_1") (pintype "passive"))
      (node (ref "FB9") (pin "1") (pinfunction "1_1") (pintype "passive"))
      (node (ref "J8") (pin "1") (pinfunction "1_1") (pintype "input"))
      (node (ref "R10") (pin "2") (pinfunction "2_2") (pintype "passive"))
      (node (ref "R4") (pin "1") (pinfunction "1_1") (pintype "passive"))
      (node (ref "R5") (pin "1") (pinfunction "1_1") (pintype "passive"))
      (node (ref "R6") (pin "1") (pinfunction "1_1") (pintype "passive"))
      (node (ref "R7") (pin "2") (pinfunction "2_2") (pintype "passive"))
      (node (ref "R8") (pin "1") (pinfunction "1_1") (pintype "passive"))
    )
    (net (code "75") (name "GND") (class "Default")
      (node (ref "C22") (pin "2") (pinfunction "2_2") (pintype "passive"))
      (node (ref "C23") (pin "2") (pinfunction "2_2") (pintype "passive"))
      (node (ref "C24") (pin "2") (pinfunction "2_2") (pintype "passive"))
      (node (ref "C25") (pin "2") (pinfunction "2_2") (pintype "passive"))
      (node (ref "C26") (pin "2") (pinfunction "2_2") (pintype "passive"))
      (node (ref "C27") (pin "2") (pinfunction "2_2") (pintype "passive"))
      (node (ref "C28") (pin "2") (pinfunction "2_2") (pintype "passive"))
      (node (ref "C29") (pin "2") (pinfunction "2_2") (pintype "passive"))
      (node (ref "C30") (pin "2") (pinfunction "2_2") (pintype "passive"))
      (node (ref "C31") (pin "2") (pinfunction "2_2") (pintype "passive"))
      (node (ref "C32") (pin "2") (pinfunction "2_2") (pintype "passive"))
      (node (ref "C33") (pin "2") (pinfunction "2_2") (pintype "passive"))
      (node (ref "C34") (pin "2") (pinfunction "2_2") (pintype "passive"))
      (node (ref "C35") (pin "2") (pinfunction "2_2") (pintype "passive"))
      (node (ref "C36") (pin "2") (pinfunction "2_2") (pintype "passive"))
      (node (ref "C37") (pin "2") (pinfunction "2_2") (pintype "passive"))
      (node (ref "C38") (pin "2") (pinfunction "2_2") (pintype "passive"))
      (node (ref "C39") (pin "2") (pinfunction "2_2") (pintype "passive"))
      (node (ref "C40") (pin "2") (pinfunction "2_2") (pintype "passive"))
      (node (ref "C41") (pin "2") (pinfunction "2_2") (pintype "passive"))
      (node (ref "C42") (pin "2") (pinfunction "2_2") (pintype "passive"))
      (node (ref "C43") (pin "2") (pinfunction "2_2") (pintype "passive"))
      (node (ref "C44") (pin "2") (pinfunction "2_2") (pintype "passive"))
      (node (ref "C45") (pin "2") (pinfunction "2_2") (pintype "passive"))
      (node (ref "C46") (pin "2") (pinfunction "2_2") (pintype "passive"))
      (node (ref "C47") (pin "2") (pinfunction "2_2") (pintype "passive"))
      (node (ref "C48") (pin "2") (pinfunction "2_2") (pintype "passive"))
      (node (ref "C49") (pin "2") (pinfunction "2_2") (pintype "passive"))
      (node (ref "C50") (pin "2") (pinfunction "2_2") (pintype "passive"))
      (node (ref "C51") (pin "2") (pinfunction "2_2") (pintype "passive"))
      (node (ref "C52") (pin "2") (pinfunction "2_2") (pintype "passive"))
      (node (ref "C53") (pin "2") (pinfunction "2_2") (pintype "passive"))
      (node (ref "C54") (pin "2") (pinfunction "2_2") (pintype "passive"))
      (node (ref "C55") (pin "2") (pinfunction "2_2") (pintype "passive"))
      (node (ref "C56") (pin "2") (pinfunction "2_2") (pintype "passive"))
      (node (ref "C57") (pin "2") (pinfunction "2_2") (pintype "passive"))
      (node (ref "C58") (pin "2") (pinfunction "2_2") (pintype "passive"))
      (node (ref "C59") (pin "2") (pinfunction "2_2") (pintype "passive"))
      (node (ref "C60") (pin "2") (pinfunction "2_2") (pintype "passive"))
      (node (ref "C61") (pin "2") (pinfunction "2_2") (pintype "passive"))
      (node (ref "C62") (pin "2") (pinfunction "2_2") (pintype "passive"))
      (node (ref "C63") (pin "2") (pinfunction "2_2") (pintype "passive"))
      (node (ref "J8") (pin "3") (pinfunction "3_3") (pintype "input"))
      (node (ref "J8") (pin "5") (pinfunction "5_5") (pintype "input"))
      (node (ref "U1") (pin "A1") (pinfunction "VSS_1_A1") (pintype "passive"))
      (node (ref "U1") (pin "A14") (pinfunction "VSS_2_A14") (pintype "passive"))
      (node (ref "U1") (pin "B10") (pinfunction "MII2_RX_ER_B10") (pintype "passive"))
      (node (ref "U1") (pin "B13") (pinfunction "VSS_3_B13") (pintype "passive"))
      (node (ref "U1") (pin "B3") (pinfunction "MII1_RX_ER_B3") (pintype "passive"))
      (node (ref "U1") (pin "E10") (pinfunction "VSS_9_E10") (pintype "passive"))
      (node (ref "U1") (pin "E5") (pinfunction "VSS_4_E5") (pintype "passive"))
      (node (ref "U1") (pin "E6") (pinfunction "VSS_5_E6") (pintype "passive"))
      (node (ref "U1") (pin "E7") (pinfunction "VSS_6_E7") (pintype "passive"))
      (node (ref "U1") (pin "E8") (pinfunction "VSS_7_E8") (pintype "passive"))
      (node (ref "U1") (pin "E9") (pinfunction "VSS_8_E9") (pintype "passive"))
      (node (ref "U1") (pin "F10") (pinfunction "VSS_15_F10") (pintype "passive"))
      (node (ref "U1") (pin "F13") (pinfunction "MII3_RX_ER_F13") (pintype "passive"))
      (node (ref "U1") (pin "F5") (pinfunction "VSS_10_F5") (pintype "passive"))
      (node (ref "U1") (pin "F6") (pinfunction "VSS_11_F6") (pintype "passive"))
      (node (ref "U1") (pin "F7") (pinfunction "VSS_12_F7") (pintype "passive"))
      (node (ref "U1") (pin "F8") (pinfunction "VSS_13_F8") (pintype "passive"))
      (node (ref "U1") (pin "F9") (pinfunction "VSS_14_F9") (pintype "passive"))
      (node (ref "U1") (pin "G10") (pinfunction "VSS_21_G10") (pintype "passive"))
      (node (ref "U1") (pin "G5") (pinfunction "VSS_16_G5") (pintype "passive"))
      (node (ref "U1") (pin "G6") (pinfunction "VSS_17_G6") (pintype "passive"))
      (node (ref "U1") (pin "G7") (pinfunction "VSS_18_G7") (pintype "passive"))
      (node (ref "U1") (pin "G8") (pinfunction "VSS_19_G8") (pintype "passive"))
      (node (ref "U1") (pin "G9") (pinfunction "VSS_20_G9") (pintype "passive"))
      (node (ref "U1") (pin "H10") (pinfunction "VSS_27_H10") (pintype "passive"))
      (node (ref "U1") (pin "H2") (pinfunction "MII0_RX_ER_H2") (pintype "passive"))
      (node (ref "U1") (pin "H5") (pinfunction "VSS_22_H5") (pintype "passive"))
      (node (ref "U1") (pin "H6") (pinfunction "VSS_23_H6") (pintype "passive"))
      (node (ref "U1") (pin "H7") (pinfunction "VSS_24_H7") (pintype "passive"))
      (node (ref "U1") (pin "H8") (pinfunction "VSS_25_H8") (pintype "passive"))
      (node (ref "U1") (pin "H9") (pinfunction "VSS_26_H9") (pintype "passive"))
      (node (ref "U1") (pin "J10") (pinfunction "VSS_33_J10") (pintype "passive"))
      (node (ref "U1") (pin "J2") (pinfunction "VSSA_PLL_J2") (pintype "passive"))
      (node (ref "U1") (pin "J5") (pinfunction "VSS_28_J5") (pintype "passive"))
      (node (ref "U1") (pin "J6") (pinfunction "VSS_29_J6") (pintype "passive"))
      (node (ref "U1") (pin "J7") (pinfunction "VSS_30_J7") (pintype "passive"))
      (node (ref "U1") (pin "J8") (pinfunction "VSS_31_J8") (pintype "passive"))
      (node (ref "U1") (pin "J9") (pinfunction "VSS_32_J9") (pintype "passive"))
      (node (ref "U1") (pin "K10") (pinfunction "VSS_40_K10") (pintype "passive"))
      (node (ref "U1") (pin "K4") (pinfunction "VSS_34_K4") (pintype "passive"))
      (node (ref "U1") (pin "K5") (pinfunction "VSS_35_K5") (pintype "passive"))
      (node (ref "U1") (pin "K6") (pinfunction "VSS_36_K6") (pintype "passive"))
      (node (ref "U1") (pin "K7") (pinfunction "VSS_37_K7") (pintype "passive"))
      (node (ref "U1") (pin "K8") (pinfunction "VSS_38_K8") (pintype "passive"))
      (node (ref "U1") (pin "K9") (pinfunction "VSS_39_K9") (pintype "passive"))
      (node (ref "U1") (pin "L2") (pinfunction "VSSA_OSC_L2") (pintype "passive"))
      (node (ref "U1") (pin "L4") (pinfunction "I.C._(GND)_L4") (pintype "passive"))
      (node (ref "U1") (pin "L7") (pinfunction "VSS_41_L7") (pintype "passive"))
      (node (ref "U1") (pin "N13") (pinfunction "VSS_43_N13") (pintype "passive"))
      (node (ref "U1") (pin "N2") (pinfunction "VSS_42_N2") (pintype "passive"))
      (node (ref "U1") (pin "P1") (pinfunction "VSS_44_P1") (pintype "passive"))
      (node (ref "U1") (pin "P13") (pinfunction "MII4_RX_ER_P13") (pintype "passive"))
      (node (ref "U1") (pin "P14") (pinfunction "VSS_45_P14") (pintype "passive"))
      (node (ref "Y1") (pin "2") (pinfunction "GND_2") (pintype "power_in"))
      (node (ref "Y1") (pin "4") (pinfunction "GND_4") (pintype "power_in"))
    )
    (net (code "76") (name "SW_VDDA_OSC") (class "Default")
      (node (ref "C28") (pin "1") (pinfunction "1_1") (pintype "passive"))
      (node (ref "C29") (pin "1") (pinfunction "1_1") (pintype "passive"))
      (node (ref "C30") (pin "1") (pinfunction "1_1") (pintype "passive"))
      (node (ref "FB4") (pin "2") (pinfunction "2_2") (pintype "passive"))
      (node (ref "U1") (pin "K1") (pinfunction "VDDA_OSC_K1") (pintype "passive"))
    )
    (net (code "77") (name "SW_VDDA_PLL") (class "Default")
      (node (ref "C31") (pin "1") (pinfunction "1_1") (pintype "passive"))
      (node (ref "C32") (pin "1") (pinfunction "1_1") (pintype "passive"))
      (node (ref "C33") (pin "1") (pinfunction "1_1") (pintype "passive"))
      (node (ref "FB7") (pin "2") (pinfunction "2_2") (pintype "passive"))
      (node (ref "U1") (pin "J1") (pinfunction "VDDA_PLL_J1") (pintype "passive"))
    )
    (net (code "78") (name "SW_VDDIO_CLO") (class "Default")
      (node (ref "C24") (pin "1") (pinfunction "1_1") (pintype "passive"))
      (node (ref "C25") (pin "1") (pinfunction "1_1") (pintype "passive"))
      (node (ref "FB5") (pin "2") (pinfunction "2_2") (pintype "passive"))
      (node (ref "U1") (pin "L5") (pinfunction "VDDIO_HOST_L5") (pintype "passive"))
    )
    (net (code "79") (name "SW_VDDIO_HOST") (class "Default")
      (node (ref "C26") (pin "1") (pinfunction "1_1") (pintype "passive"))
      (node (ref "C27") (pin "1") (pinfunction "1_1") (pintype "passive"))
      (node (ref "FB2") (pin "2") (pinfunction "2_2") (pintype "passive"))
      (node (ref "U1") (pin "H4") (pinfunction "VDDIO_CLO_H4") (pintype "passive"))
    )
    (net (code "80") (name "SW_VDDIO_MII0") (class "Default")
      (node (ref "C44") (pin "1") (pinfunction "1_1") (pintype "passive"))
      (node (ref "C45") (pin "1") (pinfunction "1_1") (pintype "passive"))
      (node (ref "C46") (pin "1") (pinfunction "1_1") (pintype "passive"))
      (node (ref "C47") (pin "1") (pinfunction "1_1") (pintype "passive"))
      (node (ref "FB3") (pin "2") (pinfunction "2_2") (pintype "passive"))
      (node (ref "U1") (pin "D4") (pinfunction "VDDIO_MII0_1_D4") (pintype "passive"))
      (node (ref "U1") (pin "E4") (pinfunction "VDDIO_MII0_2_E4") (pintype "passive"))
      (node (ref "U1") (pin "G4") (pinfunction "VDDIO_MII0_3_G4") (pintype "passive"))
    )
    (net (code "81") (name "SW_VDDIO_MII1") (class "Default")
      (node (ref "C48") (pin "1") (pinfunction "1_1") (pintype "passive"))
      (node (ref "C49") (pin "1") (pinfunction "1_1") (pintype "passive"))
      (node (ref "C50") (pin "1") (pinfunction "1_1") (pintype "passive"))
      (node (ref "C51") (pin "1") (pinfunction "1_1") (pintype "passive"))
      (node (ref "FB6") (pin "2") (pinfunction "2_2") (pintype "passive"))
      (node (ref "U1") (pin "D5") (pinfunction "VDDIO_MII1_1_D5") (pintype "passive"))
      (node (ref "U1") (pin "D7") (pinfunction "VDDIO_MII1_2_D7") (pintype "passive"))
      (node (ref "U1") (pin "D8") (pinfunction "VDDIO_MII1_3_D8") (pintype "passive"))
    )
    (net (code "82") (name "SW_VDDIO_MII2") (class "Default")
      (node (ref "C52") (pin "1") (pinfunction "1_1") (pintype "passive"))
      (node (ref "C53") (pin "1") (pinfunction "1_1") (pintype "passive"))
      (node (ref "C54") (pin "1") (pinfunction "1_1") (pintype "passive"))
      (node (ref "C55") (pin "1") (pinfunction "1_1") (pintype "passive"))
      (node (ref "FB8") (pin "2") (pinfunction "2_2") (pintype "passive"))
      (node (ref "U1") (pin "D10") (pinfunction "VDDIO_MII2_1_D10") (pintype "passive"))
      (node (ref "U1") (pin "D11") (pinfunction "VDDIO_MII2_2_D11") (pintype "passive"))
      (node (ref "U1") (pin "E11") (pinfunction "VDDIO_MII2_3_E11") (pintype "passive"))
    )
    (net (code "83") (name "SW_VDDIO_MII3") (class "Default")
      (node (ref "C56") (pin "1") (pinfunction "1_1") (pintype "passive"))
      (node (ref "C57") (pin "1") (pinfunction "1_1") (pintype "passive"))
      (node (ref "C58") (pin "1") (pinfunction "1_1") (pintype "passive"))
      (node (ref "C59") (pin "1") (pinfunction "1_1") (pintype "passive"))
      (node (ref "FB9") (pin "2") (pinfunction "2_2") (pintype "passive"))
      (node (ref "U1") (pin "G11") (pinfunction "VDDIO_MII3_1_G11") (pintype "passive"))
      (node (ref "U1") (pin "H11") (pinfunction "VDDIO_MII3_2_H11") (pintype "passive"))
      (node (ref "U1") (pin "K11") (pinfunction "VDDIO_MII3_3_K11") (pintype "passive"))
    )
    (net (code "84") (name "SW_VDDIO_MII4") (class "Default")
      (node (ref "C60") (pin "1") (pinfunction "1_1") (pintype "passive"))
      (node (ref "C61") (pin "1") (pinfunction "1_1") (pintype "passive"))
      (node (ref "C62") (pin "1") (pinfunction "1_1") (pintype "passive"))
      (node (ref "C63") (pin "1") (pinfunction "1_1") (pintype "passive"))
      (node (ref "FB10") (pin "2") (pinfunction "2_2") (pintype "passive"))
      (node (ref "U1") (pin "L10") (pinfunction "VDDIO_MII4_2_L10") (pintype "passive"))
      (node (ref "U1") (pin "L11") (pinfunction "VDDIO_MII4_3_L11") (pintype "passive"))
      (node (ref "U1") (pin "L8") (pinfunction "VDDIO_MII4_1_L8") (pintype "passive"))
    )
    (net (code "85") (name "SW_VDD_CORE") (class "Default")
      (node (ref "C34") (pin "1") (pinfunction "1_1") (pintype "passive"))
      (node (ref "C35") (pin "1") (pinfunction "1_1") (pintype "passive"))
      (node (ref "C36") (pin "1") (pinfunction "1_1") (pintype "passive"))
      (node (ref "C37") (pin "1") (pinfunction "1_1") (pintype "passive"))
      (node (ref "C38") (pin "1") (pinfunction "1_1") (pintype "passive"))
      (node (ref "C39") (pin "1") (pinfunction "1_1") (pintype "passive"))
      (node (ref "C40") (pin "1") (pinfunction "1_1") (pintype "passive"))
      (node (ref "C41") (pin "1") (pinfunction "1_1") (pintype "passive"))
      (node (ref "C42") (pin "1") (pinfunction "1_1") (pintype "passive"))
      (node (ref "C43") (pin "1") (pinfunction "1_1") (pintype "passive"))
      (node (ref "FB1") (pin "2") (pinfunction "2_2") (pintype "passive"))
      (node (ref "U1") (pin "D6") (pinfunction "VDD_CORE_1_D6") (pintype "passive"))
      (node (ref "U1") (pin "D9") (pinfunction "VDD_CORE_2_D9") (pintype "passive"))
      (node (ref "U1") (pin "F11") (pinfunction "VDD_CORE_4_F11") (pintype "passive"))
      (node (ref "U1") (pin "F4") (pinfunction "VDD_CORE_3_F4") (pintype "passive"))
      (node (ref "U1") (pin "J11") (pinfunction "VDD_CORE_6_J11") (pintype "passive"))
      (node (ref "U1") (pin "J4") (pinfunction "VDD_CORE_5_J4") (pintype "passive"))
      (node (ref "U1") (pin "L6") (pinfunction "VDD_CORE_7_L6") (pintype "passive"))
      (node (ref "U1") (pin "L9") (pinfunction "VDD_CORE_8_L9") (pintype "passive"))
    )
    (net (code "86") (name "unconnected-(J8-Pad7)") (class "Default")
      (node (ref "J8") (pin "7") (pinfunction "7_7") (pintype "input+no_connect"))
    )
    (net (code "87") (name "unconnected-(J8-Pad9)") (class "Default")
      (node (ref "J8") (pin "9") (pinfunction "9_9") (pintype "input+no_connect"))
    )
    (net (code "88") (name "unconnected-(U1A-CLK_OUT-PadH1)") (class "Default")
      (node (ref "U1") (pin "H1") (pinfunction "CLK_OUT_H1") (pintype "passive+no_connect"))
    )
    (net (code "89") (name "unconnected-(U1A-MII0_TX_ER-PadA3)") (class "Default")
      (node (ref "U1") (pin "A3") (pinfunction "MII0_TX_ER_A3") (pintype "passive+no_connect"))
    )
    (net (code "90") (name "unconnected-(U1A-MII1_TX_ER-PadA10)") (class "Default")
      (node (ref "U1") (pin "A10") (pinfunction "MII1_TX_ER_A10") (pintype "passive+no_connect"))
    )
    (net (code "91") (name "unconnected-(U1A-MII2_TX_ER-PadF14)") (class "Default")
      (node (ref "U1") (pin "F14") (pinfunction "MII2_TX_ER_F14") (pintype "passive+no_connect"))
    )
    (net (code "92") (name "unconnected-(U1A-MII3_TX_ER-PadN14)") (class "Default")
      (node (ref "U1") (pin "N14") (pinfunction "MII3_TX_ER_N14") (pintype "passive+no_connect"))
    )
    (net (code "93") (name "unconnected-(U1A-MII4_TX_ER-PadP6)") (class "Default")
      (node (ref "U1") (pin "P6") (pinfunction "MII4_TX_ER_P6") (pintype "passive+no_connect"))
    )
    (net (code "94") (name "unconnected-(U1A-PTP_CLK-PadN4)") (class "Default")
      (node (ref "U1") (pin "N4") (pinfunction "PTP_CLK_N4") (pintype "passive+no_connect"))
    )
  )
)
